# DEMO.net
KiCad netlist of a schematic drawn in Altium Designer
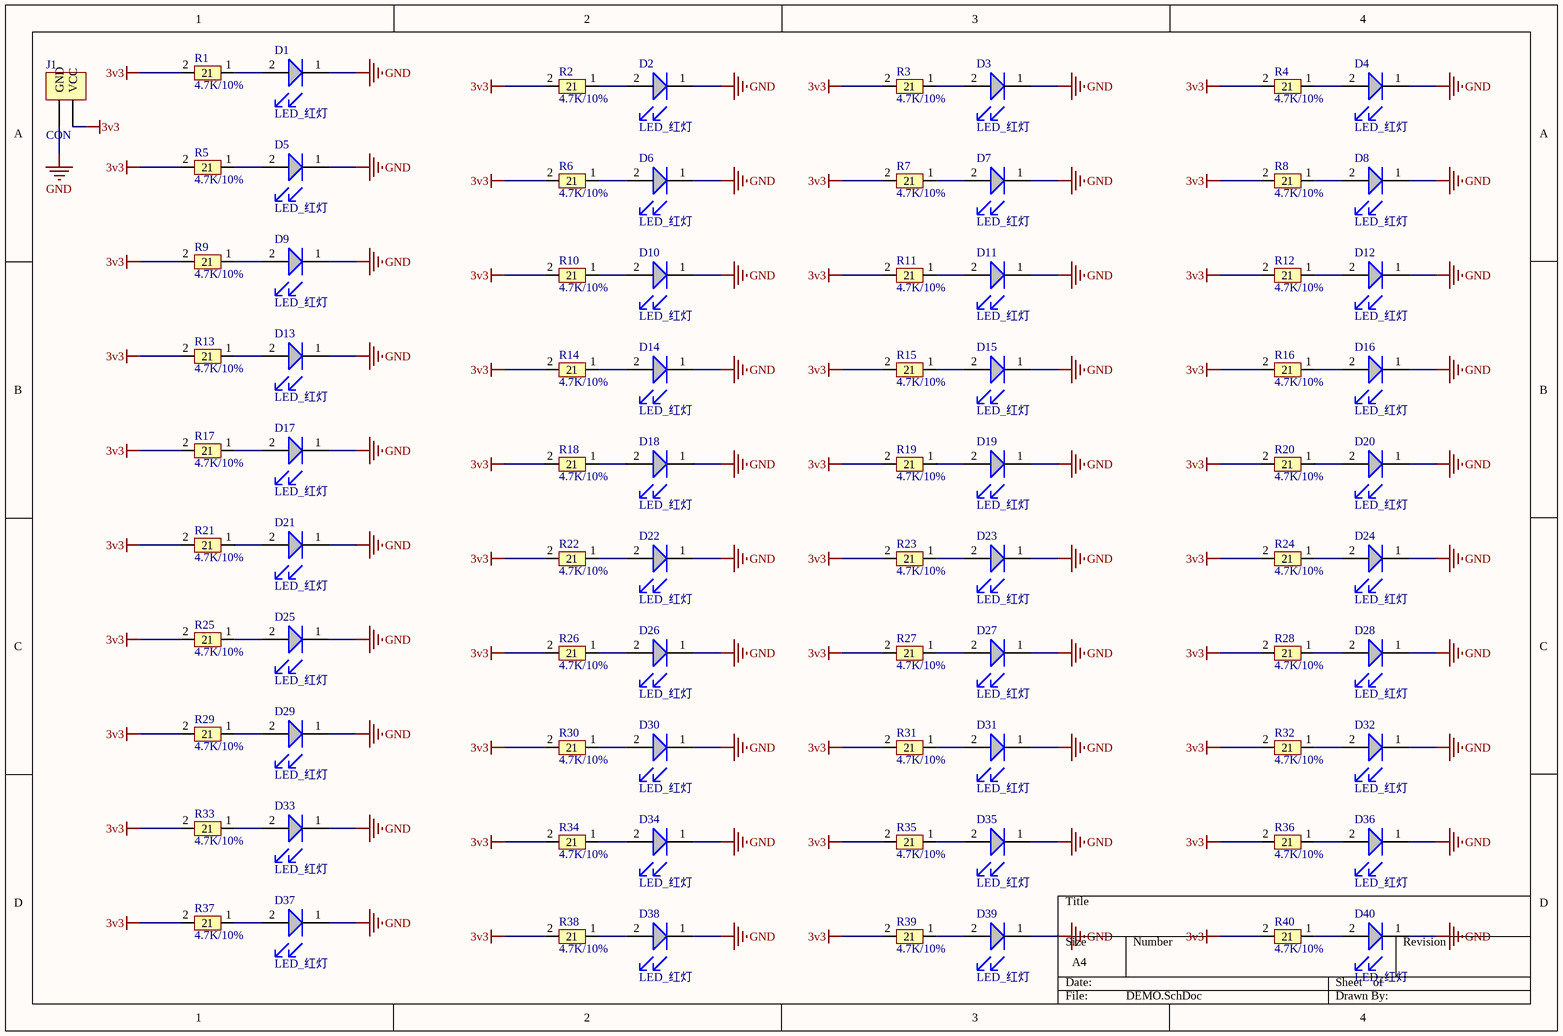
[diagram p0: DEMO.SchDoc]

(export (version "E")
  (design (tool "Eeschema 10.0.6"))
  (components
    (comp (ref "D1") (value "LED_红灯") (footprint "LED_0603") (libsource (lib "DEMO") (part "LED")))
    (comp (ref "D2") (value "LED_红灯") (footprint "LED_0603") (libsource (lib "DEMO") (part "LED")))
    (comp (ref "D3") (value "LED_红灯") (footprint "LED_0603") (libsource (lib "DEMO") (part "LED")))
    (comp (ref "D4") (value "LED_红灯") (footprint "LED_0603") (libsource (lib "DEMO") (part "LED")))
    (comp (ref "D5") (value "LED_红灯") (footprint "LED_0603") (libsource (lib "DEMO") (part "LED")))
    (comp (ref "D6") (value "LED_红灯") (footprint "LED_0603") (libsource (lib "DEMO") (part "LED")))
    (comp (ref "D7") (value "LED_红灯") (footprint "LED_0603") (libsource (lib "DEMO") (part "LED")))
    (comp (ref "D8") (value "LED_红灯") (footprint "LED_0603") (libsource (lib "DEMO") (part "LED")))
    (comp (ref "D9") (value "LED_红灯") (footprint "LED_0603") (libsource (lib "DEMO") (part "LED")))
    (comp (ref "D10") (value "LED_红灯") (footprint "LED_0603") (libsource (lib "DEMO") (part "LED")))
    (comp (ref "D11") (value "LED_红灯") (footprint "LED_0603") (libsource (lib "DEMO") (part "LED")))
    (comp (ref "D12") (value "LED_红灯") (footprint "LED_0603") (libsource (lib "DEMO") (part "LED")))
    (comp (ref "D13") (value "LED_红灯") (footprint "LED_0603") (libsource (lib "DEMO") (part "LED")))
    (comp (ref "D14") (value "LED_红灯") (footprint "LED_0603") (libsource (lib "DEMO") (part "LED")))
    (comp (ref "D15") (value "LED_红灯") (footprint "LED_0603") (libsource (lib "DEMO") (part "LED")))
    (comp (ref "D16") (value "LED_红灯") (footprint "LED_0603") (libsource (lib "DEMO") (part "LED")))
    (comp (ref "D17") (value "LED_红灯") (footprint "LED_0603") (libsource (lib "DEMO") (part "LED")))
    (comp (ref "D18") (value "LED_红灯") (footprint "LED_0603") (libsource (lib "DEMO") (part "LED")))
    (comp (ref "D19") (value "LED_红灯") (footprint "LED_0603") (libsource (lib "DEMO") (part "LED")))
    (comp (ref "D20") (value "LED_红灯") (footprint "LED_0603") (libsource (lib "DEMO") (part "LED")))
    (comp (ref "D21") (value "LED_红灯") (footprint "LED_0603") (libsource (lib "DEMO") (part "LED")))
    (comp (ref "D22") (value "LED_红灯") (footprint "LED_0603") (libsource (lib "DEMO") (part "LED")))
    (comp (ref "D23") (value "LED_红灯") (footprint "LED_0603") (libsource (lib "DEMO") (part "LED")))
    (comp (ref "D24") (value "LED_红灯") (footprint "LED_0603") (libsource (lib "DEMO") (part "LED")))
    (comp (ref "D25") (value "LED_红灯") (footprint "LED_0603") (libsource (lib "DEMO") (part "LED")))
    (comp (ref "D26") (value "LED_红灯") (footprint "LED_0603") (libsource (lib "DEMO") (part "LED")))
    (comp (ref "D27") (value "LED_红灯") (footprint "LED_0603") (libsource (lib "DEMO") (part "LED")))
    (comp (ref "D28") (value "LED_红灯") (footprint "LED_0603") (libsource (lib "DEMO") (part "LED")))
    (comp (ref "D29") (value "LED_红灯") (footprint "LED_0603") (libsource (lib "DEMO") (part "LED")))
    (comp (ref "D30") (value "LED_红灯") (footprint "LED_0603") (libsource (lib "DEMO") (part "LED")))
    (comp (ref "D31") (value "LED_红灯") (footprint "LED_0603") (libsource (lib "DEMO") (part "LED")))
    (comp (ref "D32") (value "LED_红灯") (footprint "LED_0603") (libsource (lib "DEMO") (part "LED")))
    (comp (ref "D33") (value "LED_红灯") (footprint "LED_0603") (libsource (lib "DEMO") (part "LED")))
    (comp (ref "D34") (value "LED_红灯") (footprint "LED_0603") (libsource (lib "DEMO") (part "LED")))
    (comp (ref "D35") (value "LED_红灯") (footprint "LED_0603") (libsource (lib "DEMO") (part "LED")))
    (comp (ref "D36") (value "LED_红灯") (footprint "LED_0603") (libsource (lib "DEMO") (part "LED")))
    (comp (ref "D37") (value "LED_红灯") (footprint "LED_0603") (libsource (lib "DEMO") (part "LED")))
    (comp (ref "D38") (value "LED_红灯") (footprint "LED_0603") (libsource (lib "DEMO") (part "LED")))
    (comp (ref "D39") (value "LED_红灯") (footprint "LED_0603") (libsource (lib "DEMO") (part "LED")))
    (comp (ref "D40") (value "LED_红灯") (footprint "LED_0603") (libsource (lib "DEMO") (part "LED")))
    (comp (ref "J1") (value "CON") (footprint "CON") (libsource (lib "DEMO") (part "CON")))
    (comp (ref "R1") (value "4.7K/10%") (footprint "RES_0603") (libsource (lib "DEMO") (part "RES")))
    (comp (ref "R2") (value "4.7K/10%") (footprint "RES_0603") (libsource (lib "DEMO") (part "RES")))
    (comp (ref "R3") (value "4.7K/10%") (footprint "RES_0603") (libsource (lib "DEMO") (part "RES")))
    (comp (ref "R4") (value "4.7K/10%") (footprint "RES_0603") (libsource (lib "DEMO") (part "RES")))
    (comp (ref "R5") (value "4.7K/10%") (footprint "RES_0603") (libsource (lib "DEMO") (part "RES")))
    (comp (ref "R6") (value "4.7K/10%") (footprint "RES_0603") (libsource (lib "DEMO") (part "RES")))
    (comp (ref "R7") (value "4.7K/10%") (footprint "RES_0603") (libsource (lib "DEMO") (part "RES")))
    (comp (ref "R8") (value "4.7K/10%") (footprint "RES_0603") (libsource (lib "DEMO") (part "RES")))
    (comp (ref "R9") (value "4.7K/10%") (footprint "RES_0603") (libsource (lib "DEMO") (part "RES")))
    (comp (ref "R10") (value "4.7K/10%") (footprint "RES_0603") (libsource (lib "DEMO") (part "RES")))
    (comp (ref "R11") (value "4.7K/10%") (footprint "RES_0603") (libsource (lib "DEMO") (part "RES")))
    (comp (ref "R12") (value "4.7K/10%") (footprint "RES_0603") (libsource (lib "DEMO") (part "RES")))
    (comp (ref "R13") (value "4.7K/10%") (footprint "RES_0603") (libsource (lib "DEMO") (part "RES")))
    (comp (ref "R14") (value "4.7K/10%") (footprint "RES_0603") (libsource (lib "DEMO") (part "RES")))
    (comp (ref "R15") (value "4.7K/10%") (footprint "RES_0603") (libsource (lib "DEMO") (part "RES")))
    (comp (ref "R16") (value "4.7K/10%") (footprint "RES_0603") (libsource (lib "DEMO") (part "RES")))
    (comp (ref "R17") (value "4.7K/10%") (footprint "RES_0603") (libsource (lib "DEMO") (part "RES")))
    (comp (ref "R18") (value "4.7K/10%") (footprint "RES_0603") (libsource (lib "DEMO") (part "RES")))
    (comp (ref "R19") (value "4.7K/10%") (footprint "RES_0603") (libsource (lib "DEMO") (part "RES")))
    (comp (ref "R20") (value "4.7K/10%") (footprint "RES_0603") (libsource (lib "DEMO") (part "RES")))
    (comp (ref "R21") (value "4.7K/10%") (footprint "RES_0603") (libsource (lib "DEMO") (part "RES")))
    (comp (ref "R22") (value "4.7K/10%") (footprint "RES_0603") (libsource (lib "DEMO") (part "RES")))
    (comp (ref "R23") (value "4.7K/10%") (footprint "RES_0603") (libsource (lib "DEMO") (part "RES")))
    (comp (ref "R24") (value "4.7K/10%") (footprint "RES_0603") (libsource (lib "DEMO") (part "RES")))
    (comp (ref "R25") (value "4.7K/10%") (footprint "RES_0603") (libsource (lib "DEMO") (part "RES")))
    (comp (ref "R26") (value "4.7K/10%") (footprint "RES_0603") (libsource (lib "DEMO") (part "RES")))
    (comp (ref "R27") (value "4.7K/10%") (footprint "RES_0603") (libsource (lib "DEMO") (part "RES")))
    (comp (ref "R28") (value "4.7K/10%") (footprint "RES_0603") (libsource (lib "DEMO") (part "RES")))
    (comp (ref "R29") (value "4.7K/10%") (footprint "RES_0603") (libsource (lib "DEMO") (part "RES")))
    (comp (ref "R30") (value "4.7K/10%") (footprint "RES_0603") (libsource (lib "DEMO") (part "RES")))
    (comp (ref "R31") (value "4.7K/10%") (footprint "RES_0603") (libsource (lib "DEMO") (part "RES")))
    (comp (ref "R32") (value "4.7K/10%") (footprint "RES_0603") (libsource (lib "DEMO") (part "RES")))
    (comp (ref "R33") (value "4.7K/10%") (footprint "RES_0603") (libsource (lib "DEMO") (part "RES")))
    (comp (ref "R34") (value "4.7K/10%") (footprint "RES_0603") (libsource (lib "DEMO") (part "RES")))
    (comp (ref "R35") (value "4.7K/10%") (footprint "RES_0603") (libsource (lib "DEMO") (part "RES")))
    (comp (ref "R36") (value "4.7K/10%") (footprint "RES_0603") (libsource (lib "DEMO") (part "RES")))
    (comp (ref "R37") (value "4.7K/10%") (footprint "RES_0603") (libsource (lib "DEMO") (part "RES")))
    (comp (ref "R38") (value "4.7K/10%") (footprint "RES_0603") (libsource (lib "DEMO") (part "RES")))
    (comp (ref "R39") (value "4.7K/10%") (footprint "RES_0603") (libsource (lib "DEMO") (part "RES")))
    (comp (ref "R40") (value "4.7K/10%") (footprint "RES_0603") (libsource (lib "DEMO") (part "RES")))
  )
  (nets
    (net (code "1") (name "3v3") (class "Default")
      (node (ref "J1") (pin "1") (pinfunction "VCC_1") (pintype "passive"))
      (node (ref "R1") (pin "2") (pinfunction "2_2") (pintype "passive"))
      (node (ref "R10") (pin "2") (pinfunction "2_2") (pintype "passive"))
      (node (ref "R11") (pin "2") (pinfunction "2_2") (pintype "passive"))
      (node (ref "R12") (pin "2") (pinfunction "2_2") (pintype "passive"))
      (node (ref "R13") (pin "2") (pinfunction "2_2") (pintype "passive"))
      (node (ref "R14") (pin "2") (pinfunction "2_2") (pintype "passive"))
      (node (ref "R15") (pin "2") (pinfunction "2_2") (pintype "passive"))
      (node (ref "R16") (pin "2") (pinfunction "2_2") (pintype "passive"))
      (node (ref "R17") (pin "2") (pinfunction "2_2") (pintype "passive"))
      (node (ref "R18") (pin "2") (pinfunction "2_2") (pintype "passive"))
      (node (ref "R19") (pin "2") (pinfunction "2_2") (pintype "passive"))
      (node (ref "R2") (pin "2") (pinfunction "2_2") (pintype "passive"))
      (node (ref "R20") (pin "2") (pinfunction "2_2") (pintype "passive"))
      (node (ref "R21") (pin "2") (pinfunction "2_2") (pintype "passive"))
      (node (ref "R22") (pin "2") (pinfunction "2_2") (pintype "passive"))
      (node (ref "R23") (pin "2") (pinfunction "2_2") (pintype "passive"))
      (node (ref "R24") (pin "2") (pinfunction "2_2") (pintype "passive"))
      (node (ref "R25") (pin "2") (pinfunction "2_2") (pintype "passive"))
      (node (ref "R26") (pin "2") (pinfunction "2_2") (pintype "passive"))
      (node (ref "R27") (pin "2") (pinfunction "2_2") (pintype "passive"))
      (node (ref "R28") (pin "2") (pinfunction "2_2") (pintype "passive"))
      (node (ref "R29") (pin "2") (pinfunction "2_2") (pintype "passive"))
      (node (ref "R3") (pin "2") (pinfunction "2_2") (pintype "passive"))
      (node (ref "R30") (pin "2") (pinfunction "2_2") (pintype "passive"))
      (node (ref "R31") (pin "2") (pinfunction "2_2") (pintype "passive"))
      (node (ref "R32") (pin "2") (pinfunction "2_2") (pintype "passive"))
      (node (ref "R33") (pin "2") (pinfunction "2_2") (pintype "passive"))
      (node (ref "R34") (pin "2") (pinfunction "2_2") (pintype "passive"))
      (node (ref "R35") (pin "2") (pinfunction "2_2") (pintype "passive"))
      (node (ref "R36") (pin "2") (pinfunction "2_2") (pintype "passive"))
      (node (ref "R37") (pin "2") (pinfunction "2_2") (pintype "passive"))
      (node (ref "R38") (pin "2") (pinfunction "2_2") (pintype "passive"))
      (node (ref "R39") (pin "2") (pinfunction "2_2") (pintype "passive"))
      (node (ref "R4") (pin "2") (pinfunction "2_2") (pintype "passive"))
      (node (ref "R40") (pin "2") (pinfunction "2_2") (pintype "passive"))
      (node (ref "R5") (pin "2") (pinfunction "2_2") (pintype "passive"))
      (node (ref "R6") (pin "2") (pinfunction "2_2") (pintype "passive"))
      (node (ref "R7") (pin "2") (pinfunction "2_2") (pintype "passive"))
      (node (ref "R8") (pin "2") (pinfunction "2_2") (pintype "passive"))
      (node (ref "R9") (pin "2") (pinfunction "2_2") (pintype "passive"))
    )
    (net (code "2") (name "GND") (class "Default")
      (node (ref "D1") (pin "1") (pinfunction "1_1") (pintype "passive"))
      (node (ref "D10") (pin "1") (pinfunction "1_1") (pintype "passive"))
      (node (ref "D11") (pin "1") (pinfunction "1_1") (pintype "passive"))
      (node (ref "D12") (pin "1") (pinfunction "1_1") (pintype "passive"))
      (node (ref "D13") (pin "1") (pinfunction "1_1") (pintype "passive"))
      (node (ref "D14") (pin "1") (pinfunction "1_1") (pintype "passive"))
      (node (ref "D15") (pin "1") (pinfunction "1_1") (pintype "passive"))
      (node (ref "D16") (pin "1") (pinfunction "1_1") (pintype "passive"))
      (node (ref "D17") (pin "1") (pinfunction "1_1") (pintype "passive"))
      (node (ref "D18") (pin "1") (pinfunction "1_1") (pintype "passive"))
      (node (ref "D19") (pin "1") (pinfunction "1_1") (pintype "passive"))
      (node (ref "D2") (pin "1") (pinfunction "1_1") (pintype "passive"))
      (node (ref "D20") (pin "1") (pinfunction "1_1") (pintype "passive"))
      (node (ref "D21") (pin "1") (pinfunction "1_1") (pintype "passive"))
      (node (ref "D22") (pin "1") (pinfunction "1_1") (pintype "passive"))
      (node (ref "D23") (pin "1") (pinfunction "1_1") (pintype "passive"))
      (node (ref "D24") (pin "1") (pinfunction "1_1") (pintype "passive"))
      (node (ref "D25") (pin "1") (pinfunction "1_1") (pintype "passive"))
      (node (ref "D26") (pin "1") (pinfunction "1_1") (pintype "passive"))
      (node (ref "D27") (pin "1") (pinfunction "1_1") (pintype "passive"))
      (node (ref "D28") (pin "1") (pinfunction "1_1") (pintype "passive"))
      (node (ref "D29") (pin "1") (pinfunction "1_1") (pintype "passive"))
      (node (ref "D3") (pin "1") (pinfunction "1_1") (pintype "passive"))
      (node (ref "D30") (pin "1") (pinfunction "1_1") (pintype "passive"))
      (node (ref "D31") (pin "1") (pinfunction "1_1") (pintype "passive"))
      (node (ref "D32") (pin "1") (pinfunction "1_1") (pintype "passive"))
      (node (ref "D33") (pin "1") (pinfunction "1_1") (pintype "passive"))
      (node (ref "D34") (pin "1") (pinfunction "1_1") (pintype "passive"))
      (node (ref "D35") (pin "1") (pinfunction "1_1") (pintype "passive"))
      (node (ref "D36") (pin "1") (pinfunction "1_1") (pintype "passive"))
      (node (ref "D37") (pin "1") (pinfunction "1_1") (pintype "passive"))
      (node (ref "D38") (pin "1") (pinfunction "1_1") (pintype "passive"))
      (node (ref "D39") (pin "1") (pinfunction "1_1") (pintype "passive"))
      (node (ref "D4") (pin "1") (pinfunction "1_1") (pintype "passive"))
      (node (ref "D40") (pin "1") (pinfunction "1_1") (pintype "passive"))
      (node (ref "D5") (pin "1") (pinfunction "1_1") (pintype "passive"))
      (node (ref "D6") (pin "1") (pinfunction "1_1") (pintype "passive"))
      (node (ref "D7") (pin "1") (pinfunction "1_1") (pintype "passive"))
      (node (ref "D8") (pin "1") (pinfunction "1_1") (pintype "passive"))
      (node (ref "D9") (pin "1") (pinfunction "1_1") (pintype "passive"))
      (node (ref "J1") (pin "2") (pinfunction "GND_2") (pintype "passive"))
    )
    (net (code "3") (name "Net-(D1-Pad2)") (class "Default")
      (node (ref "D1") (pin "2") (pinfunction "2_2") (pintype "passive"))
      (node (ref "R1") (pin "1") (pinfunction "1_1") (pintype "passive"))
    )
    (net (code "4") (name "Net-(D2-Pad2)") (class "Default")
      (node (ref "D2") (pin "2") (pinfunction "2_2") (pintype "passive"))
      (node (ref "R2") (pin "1") (pinfunction "1_1") (pintype "passive"))
    )
    (net (code "5") (name "Net-(D3-Pad2)") (class "Default")
      (node (ref "D3") (pin "2") (pinfunction "2_2") (pintype "passive"))
      (node (ref "R3") (pin "1") (pinfunction "1_1") (pintype "passive"))
    )
    (net (code "6") (name "Net-(D4-Pad2)") (class "Default")
      (node (ref "D4") (pin "2") (pinfunction "2_2") (pintype "passive"))
      (node (ref "R4") (pin "1") (pinfunction "1_1") (pintype "passive"))
    )
    (net (code "7") (name "Net-(D5-Pad2)") (class "Default")
      (node (ref "D5") (pin "2") (pinfunction "2_2") (pintype "passive"))
      (node (ref "R5") (pin "1") (pinfunction "1_1") (pintype "passive"))
    )
    (net (code "8") (name "Net-(D6-Pad2)") (class "Default")
      (node (ref "D6") (pin "2") (pinfunction "2_2") (pintype "passive"))
      (node (ref "R6") (pin "1") (pinfunction "1_1") (pintype "passive"))
    )
    (net (code "9") (name "Net-(D7-Pad2)") (class "Default")
      (node (ref "D7") (pin "2") (pinfunction "2_2") (pintype "passive"))
      (node (ref "R7") (pin "1") (pinfunction "1_1") (pintype "passive"))
    )
    (net (code "10") (name "Net-(D8-Pad2)") (class "Default")
      (node (ref "D8") (pin "2") (pinfunction "2_2") (pintype "passive"))
      (node (ref "R8") (pin "1") (pinfunction "1_1") (pintype "passive"))
    )
    (net (code "11") (name "Net-(D9-Pad2)") (class "Default")
      (node (ref "D9") (pin "2") (pinfunction "2_2") (pintype "passive"))
      (node (ref "R9") (pin "1") (pinfunction "1_1") (pintype "passive"))
    )
    (net (code "12") (name "Net-(D10-Pad2)") (class "Default")
      (node (ref "D10") (pin "2") (pinfunction "2_2") (pintype "passive"))
      (node (ref "R10") (pin "1") (pinfunction "1_1") (pintype "passive"))
    )
    (net (code "13") (name "Net-(D11-Pad2)") (class "Default")
      (node (ref "D11") (pin "2") (pinfunction "2_2") (pintype "passive"))
      (node (ref "R11") (pin "1") (pinfunction "1_1") (pintype "passive"))
    )
    (net (code "14") (name "Net-(D12-Pad2)") (class "Default")
      (node (ref "D12") (pin "2") (pinfunction "2_2") (pintype "passive"))
      (node (ref "R12") (pin "1") (pinfunction "1_1") (pintype "passive"))
    )
    (net (code "15") (name "Net-(D13-Pad2)") (class "Default")
      (node (ref "D13") (pin "2") (pinfunction "2_2") (pintype "passive"))
      (node (ref "R13") (pin "1") (pinfunction "1_1") (pintype "passive"))
    )
    (net (code "16") (name "Net-(D14-Pad2)") (class "Default")
      (node (ref "D14") (pin "2") (pinfunction "2_2") (pintype "passive"))
      (node (ref "R14") (pin "1") (pinfunction "1_1") (pintype "passive"))
    )
    (net (code "17") (name "Net-(D15-Pad2)") (class "Default")
      (node (ref "D15") (pin "2") (pinfunction "2_2") (pintype "passive"))
      (node (ref "R15") (pin "1") (pinfunction "1_1") (pintype "passive"))
    )
    (net (code "18") (name "Net-(D16-Pad2)") (class "Default")
      (node (ref "D16") (pin "2") (pinfunction "2_2") (pintype "passive"))
      (node (ref "R16") (pin "1") (pinfunction "1_1") (pintype "passive"))
    )
    (net (code "19") (name "Net-(D17-Pad2)") (class "Default")
      (node (ref "D17") (pin "2") (pinfunction "2_2") (pintype "passive"))
      (node (ref "R17") (pin "1") (pinfunction "1_1") (pintype "passive"))
    )
    (net (code "20") (name "Net-(D18-Pad2)") (class "Default")
      (node (ref "D18") (pin "2") (pinfunction "2_2") (pintype "passive"))
      (node (ref "R18") (pin "1") (pinfunction "1_1") (pintype "passive"))
    )
    (net (code "21") (name "Net-(D19-Pad2)") (class "Default")
      (node (ref "D19") (pin "2") (pinfunction "2_2") (pintype "passive"))
      (node (ref "R19") (pin "1") (pinfunction "1_1") (pintype "passive"))
    )
    (net (code "22") (name "Net-(D20-Pad2)") (class "Default")
      (node (ref "D20") (pin "2") (pinfunction "2_2") (pintype "passive"))
      (node (ref "R20") (pin "1") (pinfunction "1_1") (pintype "passive"))
    )
    (net (code "23") (name "Net-(D21-Pad2)") (class "Default")
      (node (ref "D21") (pin "2") (pinfunction "2_2") (pintype "passive"))
      (node (ref "R21") (pin "1") (pinfunction "1_1") (pintype "passive"))
    )
    (net (code "24") (name "Net-(D22-Pad2)") (class "Default")
      (node (ref "D22") (pin "2") (pinfunction "2_2") (pintype "passive"))
      (node (ref "R22") (pin "1") (pinfunction "1_1") (pintype "passive"))
    )
    (net (code "25") (name "Net-(D23-Pad2)") (class "Default")
      (node (ref "D23") (pin "2") (pinfunction "2_2") (pintype "passive"))
      (node (ref "R23") (pin "1") (pinfunction "1_1") (pintype "passive"))
    )
    (net (code "26") (name "Net-(D24-Pad2)") (class "Default")
      (node (ref "D24") (pin "2") (pinfunction "2_2") (pintype "passive"))
      (node (ref "R24") (pin "1") (pinfunction "1_1") (pintype "passive"))
    )
    (net (code "27") (name "Net-(D25-Pad2)") (class "Default")
      (node (ref "D25") (pin "2") (pinfunction "2_2") (pintype "passive"))
      (node (ref "R25") (pin "1") (pinfunction "1_1") (pintype "passive"))
    )
    (net (code "28") (name "Net-(D26-Pad2)") (class "Default")
      (node (ref "D26") (pin "2") (pinfunction "2_2") (pintype "passive"))
      (node (ref "R26") (pin "1") (pinfunction "1_1") (pintype "passive"))
    )
    (net (code "29") (name "Net-(D27-Pad2)") (class "Default")
      (node (ref "D27") (pin "2") (pinfunction "2_2") (pintype "passive"))
      (node (ref "R27") (pin "1") (pinfunction "1_1") (pintype "passive"))
    )
    (net (code "30") (name "Net-(D28-Pad2)") (class "Default")
      (node (ref "D28") (pin "2") (pinfunction "2_2") (pintype "passive"))
      (node (ref "R28") (pin "1") (pinfunction "1_1") (pintype "passive"))
    )
    (net (code "31") (name "Net-(D29-Pad2)") (class "Default")
      (node (ref "D29") (pin "2") (pinfunction "2_2") (pintype "passive"))
      (node (ref "R29") (pin "1") (pinfunction "1_1") (pintype "passive"))
    )
    (net (code "32") (name "Net-(D30-Pad2)") (class "Default")
      (node (ref "D30") (pin "2") (pinfunction "2_2") (pintype "passive"))
      (node (ref "R30") (pin "1") (pinfunction "1_1") (pintype "passive"))
    )
    (net (code "33") (name "Net-(D31-Pad2)") (class "Default")
      (node (ref "D31") (pin "2") (pinfunction "2_2") (pintype "passive"))
      (node (ref "R31") (pin "1") (pinfunction "1_1") (pintype "passive"))
    )
    (net (code "34") (name "Net-(D32-Pad2)") (class "Default")
      (node (ref "D32") (pin "2") (pinfunction "2_2") (pintype "passive"))
      (node (ref "R32") (pin "1") (pinfunction "1_1") (pintype "passive"))
    )
    (net (code "35") (name "Net-(D33-Pad2)") (class "Default")
      (node (ref "D33") (pin "2") (pinfunction "2_2") (pintype "passive"))
      (node (ref "R33") (pin "1") (pinfunction "1_1") (pintype "passive"))
    )
    (net (code "36") (name "Net-(D34-Pad2)") (class "Default")
      (node (ref "D34") (pin "2") (pinfunction "2_2") (pintype "passive"))
      (node (ref "R34") (pin "1") (pinfunction "1_1") (pintype "passive"))
    )
    (net (code "37") (name "Net-(D35-Pad2)") (class "Default")
      (node (ref "D35") (pin "2") (pinfunction "2_2") (pintype "passive"))
      (node (ref "R35") (pin "1") (pinfunction "1_1") (pintype "passive"))
    )
    (net (code "38") (name "Net-(D36-Pad2)") (class "Default")
      (node (ref "D36") (pin "2") (pinfunction "2_2") (pintype "passive"))
      (node (ref "R36") (pin "1") (pinfunction "1_1") (pintype "passive"))
    )
    (net (code "39") (name "Net-(D37-Pad2)") (class "Default")
      (node (ref "D37") (pin "2") (pinfunction "2_2") (pintype "passive"))
      (node (ref "R37") (pin "1") (pinfunction "1_1") (pintype "passive"))
    )
    (net (code "40") (name "Net-(D38-Pad2)") (class "Default")
      (node (ref "D38") (pin "2") (pinfunction "2_2") (pintype "passive"))
      (node (ref "R38") (pin "1") (pinfunction "1_1") (pintype "passive"))
    )
    (net (code "41") (name "Net-(D39-Pad2)") (class "Default")
      (node (ref "D39") (pin "2") (pinfunction "2_2") (pintype "passive"))
      (node (ref "R39") (pin "1") (pinfunction "1_1") (pintype "passive"))
    )
    (net (code "42") (name "Net-(D40-Pad2)") (class "Default")
      (node (ref "D40") (pin "2") (pinfunction "2_2") (pintype "passive"))
      (node (ref "R40") (pin "1") (pinfunction "1_1") (pintype "passive"))
    )
  )
)
